# Sheet3.net
KiCad netlist of a schematic drawn in Altium Designer
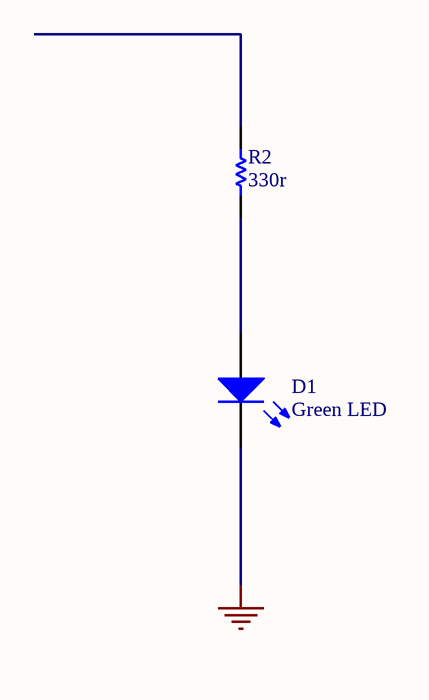
[diagram p0: Sheet3.SchDoc]

(export (version "E")
  (design (tool "Eeschema 10.0.6"))
  (components
    (comp (ref "D1")
      (value "Green LED")
      (footprint "LED-0")
      (description "Typical INFRARED GaAs LED")
      (fields (field (name "PUBLISHER") "Altium Limited"))
      (libsource (lib "Miscellaneous Devices") (part "LED0"))
    )
    (comp (ref "R2")
      (value "330r")
      (footprint "AXIAL-0.3")
      (description "Resistor")
      (fields (field (name "PUBLISHER") "Altium Limited"))
      (libsource (lib "Miscellaneous Devices") (part "Res1"))
    )
  )
  (nets
    (net (code "1") (name "GND") (class "Default")
      (node (ref "D1") (pin "2") (pinfunction "K_2") (pintype "passive"))
    )
    (net (code "2") (name "Net-(D1-A)") (class "Default")
      (node (ref "D1") (pin "1") (pinfunction "A_1") (pintype "passive"))
      (node (ref "R2") (pin "1") (pinfunction "1_1") (pintype "passive"))
    )
    (net (code "3") (name "unconnected-(R2-Pad2)") (class "Default")
      (node (ref "R2") (pin "2") (pinfunction "2_2") (pintype "passive"))
    )
  )
)
